# BlinkyBoard.net
KiCad netlist of a schematic drawn in EAGLE
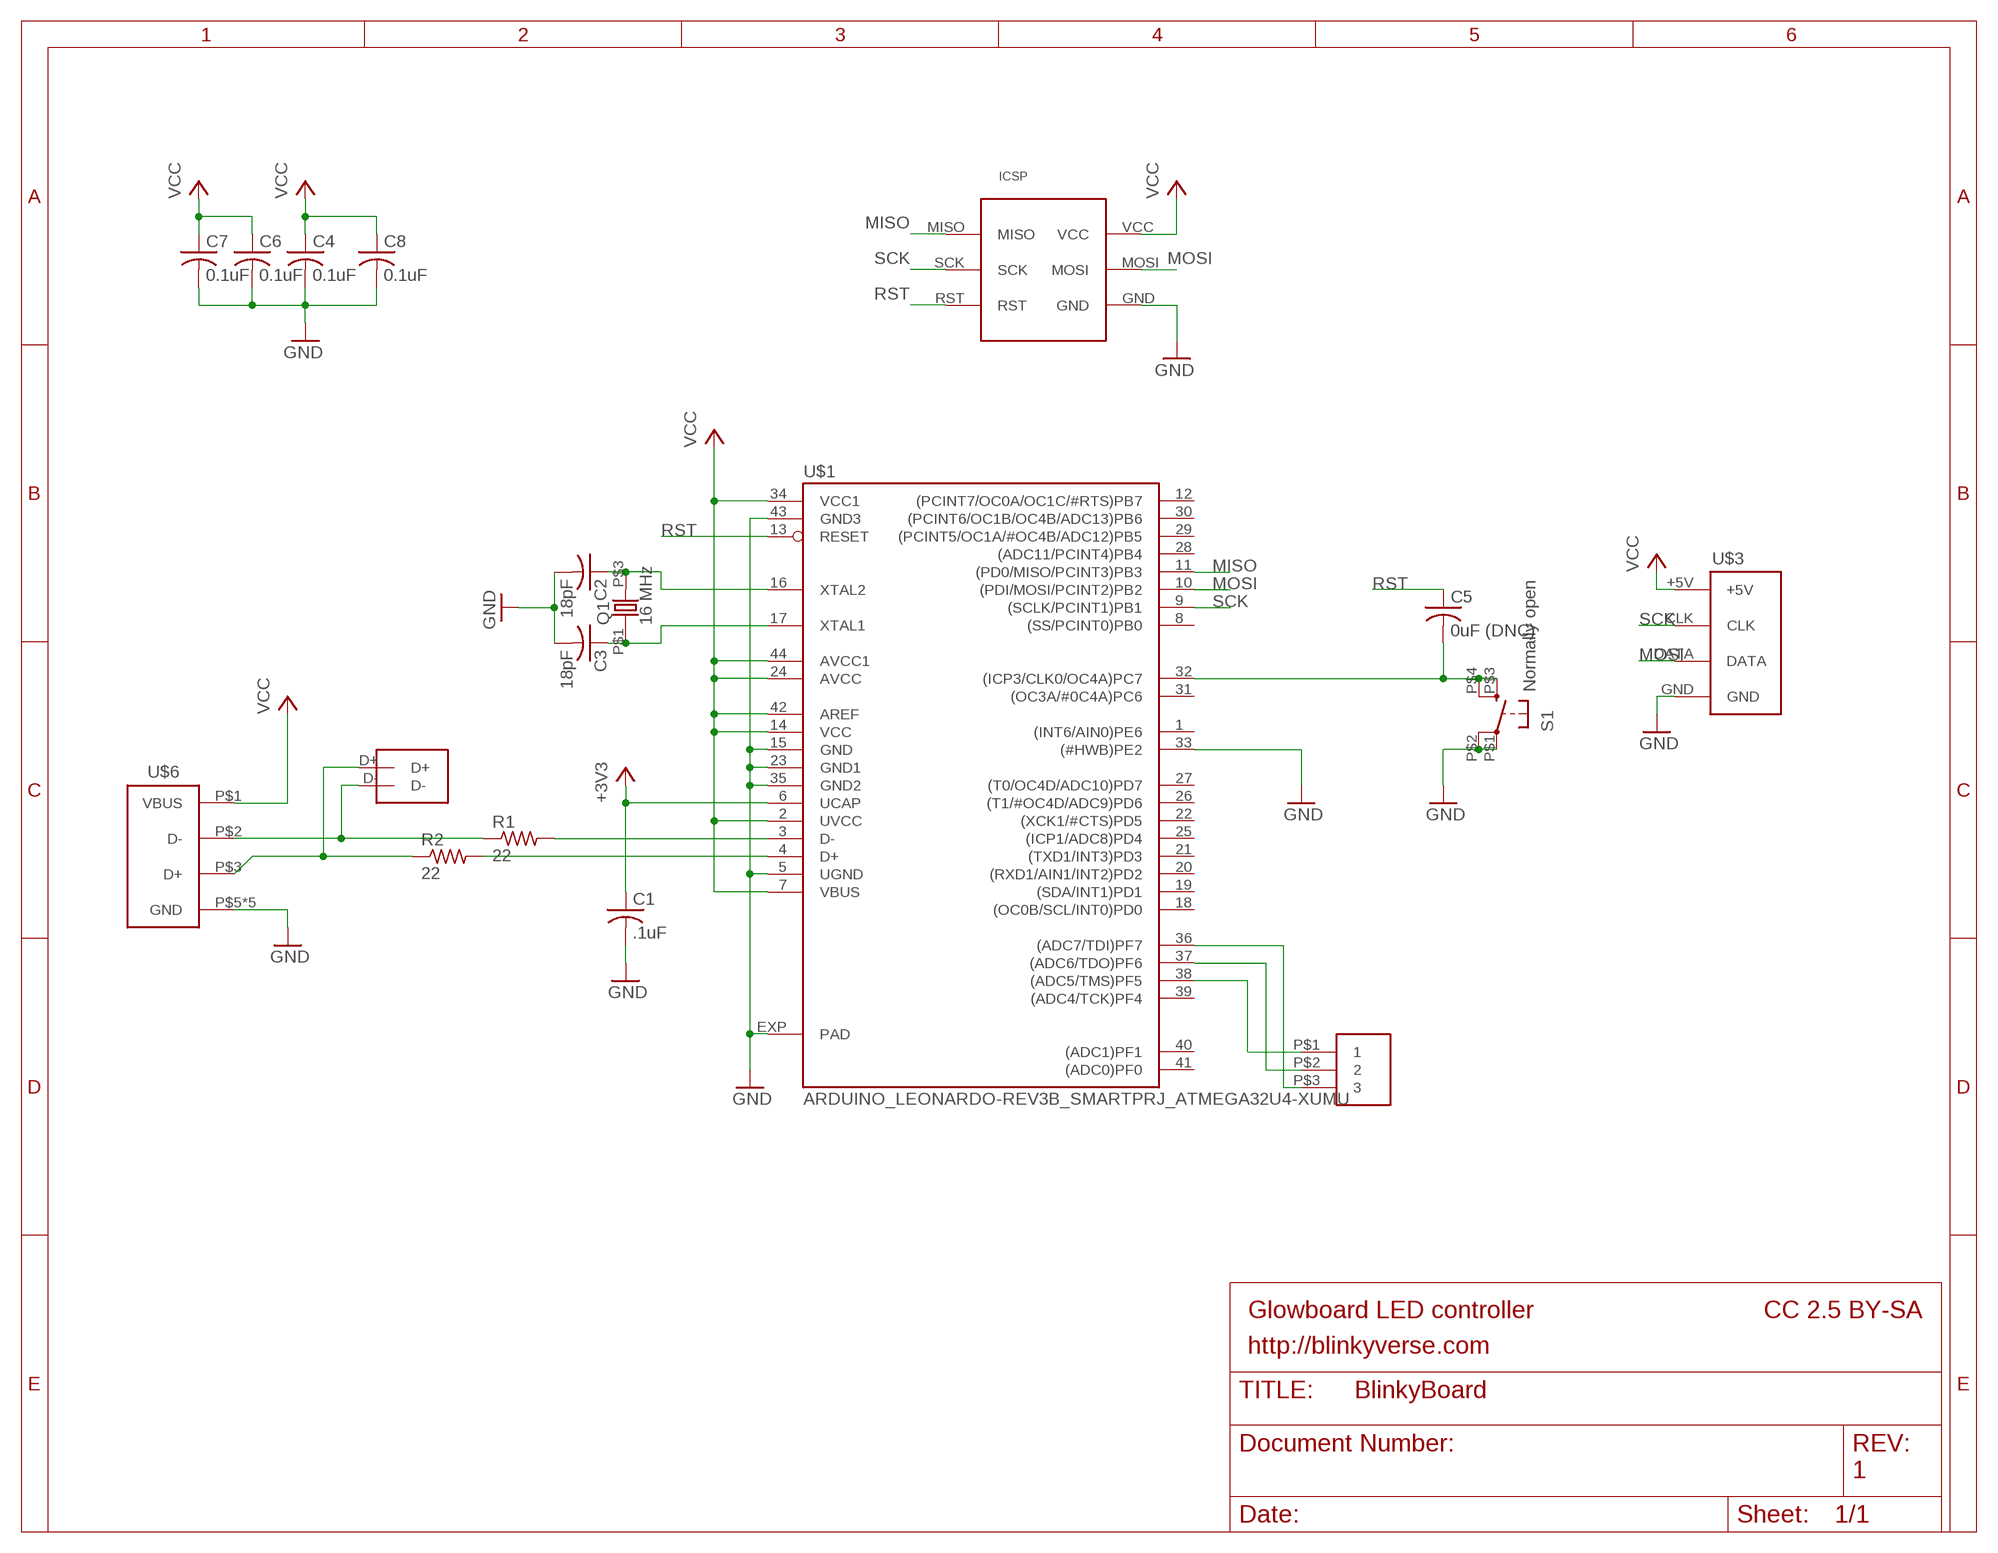
[diagram p0: schematic, sheet 1]

(export (version "E")
  (design (tool "Eeschema 10.0.6"))
  (components
    (comp (ref "C1")
      (value ".1uF")
      (footprint "eagle-import:C0805K")
      (libsource (lib "eagle-import") (part "C-USC0805K"))
    )
    (comp (ref "C2")
      (value "18pF")
      (footprint "eagle-import:C0805K")
      (libsource (lib "eagle-import") (part "C-USC0805K"))
    )
    (comp (ref "C3")
      (value "18pF")
      (footprint "eagle-import:C0805K")
      (libsource (lib "eagle-import") (part "C-USC0805K"))
    )
    (comp (ref "C4")
      (value "0.1uF")
      (footprint "eagle-import:C0805K")
      (libsource (lib "eagle-import") (part "C-USC0805K"))
    )
    (comp (ref "C5")
      (value "0uF (DNC)")
      (footprint "eagle-import:C0805K")
      (libsource (lib "eagle-import") (part "C-USC0805K"))
    )
    (comp (ref "C6")
      (value "0.1uF")
      (footprint "eagle-import:C0805K")
      (libsource (lib "eagle-import") (part "C-USC0805K"))
    )
    (comp (ref "C7")
      (value "0.1uF")
      (footprint "eagle-import:C0805K")
      (libsource (lib "eagle-import") (part "C-USC0805K"))
    )
    (comp (ref "C8")
      (value "0.1uF")
      (footprint "eagle-import:C0805K")
      (libsource (lib "eagle-import") (part "C-USC0805K"))
    )
    (comp (ref "Q1")
      (value "16 MHz")
      (footprint "eagle-import:ABMM2_CRYSTAL")
      (libsource (lib "eagle-import") (part "ABMM2"))
    )
    (comp (ref "R1")
      (value "22")
      (footprint "eagle-import:ADAFRUIT_R0805")
      (libsource (lib "eagle-import") (part "RESISTOR_0805"))
    )
    (comp (ref "R2")
      (value "22")
      (footprint "eagle-import:ADAFRUIT_R0805")
      (libsource (lib "eagle-import") (part "RESISTOR_0805"))
    )
    (comp (ref "S1")
      (value "Normally open")
      (footprint "eagle-import:GLOWBOARD_KMR211G_SWITCH")
      (libsource (lib "eagle-import") (part "GLOWBOARD_KMR211G"))
    )
    (comp (ref "U$1")
      (value "ARDUINO_LEONARDO-REV3B_SMARTPRJ_ATMEGA32U4-XUMU")
      (footprint "eagle-import:ARDUINO_LEONARDO-REV3B_SMARTPRJ_QFN44ML7X7")
      (libsource (lib "eagle-import") (part "ARDUINO_LEONARDO-REV3B_SMARTPRJ_ATMEGA32U4-XUMU"))
    )
    (comp (ref "U$2")
      (value "GLOWBOARD_USB_TEST_PADS")
      (footprint "eagle-import:GLOWBOARD_USB_TEST_PADS")
      (libsource (lib "eagle-import") (part "GLOWBOARD_USB_TEST_PADS"))
    )
    (comp (ref "U$3")
      (value "GLOWBOARD_PAD_CONNECTION")
      (footprint "eagle-import:GLOWBOARD_PAD_CONNECTION")
      (libsource (lib "eagle-import") (part "GLOWBOARD_PAD_CONNECTION"))
    )
    (comp (ref "U$4")
      (value "GLOWBOARD_ICSP")
      (footprint "eagle-import:GLOWBOARD_ICSP_PADS")
      (libsource (lib "eagle-import") (part "GLOWBOARD_ICSP"))
    )
    (comp (ref "U$5")
      (value "GLOWBOARD_EXPANSION_HEADER")
      (footprint "eagle-import:GLOWBOARD_EXPANSION_HEADER")
      (libsource (lib "eagle-import") (part "GLOWBOARD_EXPANSION_HEADER"))
    )
    (comp (ref "U$6")
      (value "GLOWBOARD_MINI_USB")
      (footprint "eagle-import:GLOWBOARD_MINI_USB_PADS")
      (libsource (lib "eagle-import") (part "GLOWBOARD_MINI_USB"))
    )
  )
  (nets
    (net (code "1") (name "+3V3") (class "Default")
      (node (ref "C1") (pin "1") (pinfunction "1_1") (pintype "passive"))
      (node (ref "U$1") (pin "6") (pinfunction "UCAP_6") (pintype "passive"))
    )
    (net (code "2") (name "/MISO") (class "Default")
      (node (ref "U$1") (pin "11") (pinfunction "(PD0/MISO/PCINT3)PB3_11") (pintype "bidirectional"))
      (node (ref "U$4") (pin "MISO") (pinfunction "MISO_MISO") (pintype "bidirectional"))
    )
    (net (code "3") (name "/MOSI") (class "Default")
      (node (ref "U$1") (pin "10") (pinfunction "(PDI/MOSI/PCINT2)PB2_10") (pintype "bidirectional"))
      (node (ref "U$3") (pin "DATA") (pinfunction "DATA_DATA") (pintype "bidirectional"))
      (node (ref "U$4") (pin "MOSI") (pinfunction "MOSI_MOSI") (pintype "bidirectional"))
    )
    (net (code "4") (name "/RST") (class "Default")
      (node (ref "C5") (pin "1") (pinfunction "1_1") (pintype "passive"))
      (node (ref "U$1") (pin "13") (pinfunction "RESET_13") (pintype "input"))
      (node (ref "U$4") (pin "RST") (pinfunction "RST_RST") (pintype "bidirectional"))
    )
    (net (code "5") (name "/SCK") (class "Default")
      (node (ref "U$1") (pin "9") (pinfunction "(SCLK/PCINT1)PB1_9") (pintype "bidirectional"))
      (node (ref "U$3") (pin "CLK") (pinfunction "CLK_CLK") (pintype "bidirectional"))
      (node (ref "U$4") (pin "SCK") (pinfunction "SCK_SCK") (pintype "bidirectional"))
    )
    (net (code "6") (name "GND") (class "Default")
      (node (ref "C1") (pin "2") (pinfunction "2_2") (pintype "passive"))
      (node (ref "C2") (pin "2") (pinfunction "2_2") (pintype "passive"))
      (node (ref "C3") (pin "2") (pinfunction "2_2") (pintype "passive"))
      (node (ref "C4") (pin "2") (pinfunction "2_2") (pintype "passive"))
      (node (ref "C6") (pin "2") (pinfunction "2_2") (pintype "passive"))
      (node (ref "C7") (pin "2") (pinfunction "2_2") (pintype "passive"))
      (node (ref "C8") (pin "2") (pinfunction "2_2") (pintype "passive"))
      (node (ref "S1") (pin "P$1") (pinfunction "P_P$1") (pintype "passive"))
      (node (ref "S1") (pin "P$2") (pinfunction "P1_P$2") (pintype "passive"))
      (node (ref "U$1") (pin "15") (pinfunction "GND_15") (pintype "power_in"))
      (node (ref "U$1") (pin "23") (pinfunction "GND1_23") (pintype "power_in"))
      (node (ref "U$1") (pin "33") (pinfunction "(#HWB)PE2_33") (pintype "bidirectional"))
      (node (ref "U$1") (pin "35") (pinfunction "GND2_35") (pintype "power_in"))
      (node (ref "U$1") (pin "43") (pinfunction "GND3_43") (pintype "power_in"))
      (node (ref "U$1") (pin "5") (pinfunction "UGND_5") (pintype "power_in"))
      (node (ref "U$1") (pin "EXP") (pinfunction "PAD_EXP") (pintype "power_in"))
      (node (ref "U$3") (pin "GND") (pinfunction "GND_GND") (pintype "bidirectional"))
      (node (ref "U$4") (pin "GND") (pinfunction "GND_GND") (pintype "bidirectional"))
      (node (ref "U$6") (pin "P$5") (pinfunction "GND_P$5") (pintype "bidirectional"))
      (node (ref "U$6") (pin "P$6") (pinfunction "GND_P$6") (pintype "bidirectional"))
      (node (ref "U$6") (pin "P$7") (pinfunction "GND_P$7") (pintype "bidirectional"))
      (node (ref "U$6") (pin "P$8") (pinfunction "GND_P$8") (pintype "bidirectional"))
      (node (ref "U$6") (pin "P$9") (pinfunction "GND_P$9") (pintype "bidirectional"))
    )
    (net (code "7") (name "Net-(Q1-1)") (class "Default")
      (node (ref "C3") (pin "1") (pinfunction "1_1") (pintype "passive"))
      (node (ref "Q1") (pin "P$1") (pinfunction "1_P$1") (pintype "passive"))
      (node (ref "U$1") (pin "17") (pinfunction "XTAL1_17") (pintype "bidirectional"))
    )
    (net (code "8") (name "Net-(Q1-2)") (class "Default")
      (node (ref "C2") (pin "1") (pinfunction "1_1") (pintype "passive"))
      (node (ref "Q1") (pin "P$3") (pinfunction "2_P$3") (pintype "passive"))
      (node (ref "U$1") (pin "16") (pinfunction "XTAL2_16") (pintype "bidirectional"))
    )
    (net (code "9") (name "Net-(S1-S)") (class "Default")
      (node (ref "C5") (pin "2") (pinfunction "2_2") (pintype "passive"))
      (node (ref "S1") (pin "P$3") (pinfunction "S_P$3") (pintype "passive"))
      (node (ref "S1") (pin "P$4") (pinfunction "S1_P$4") (pintype "passive"))
      (node (ref "U$1") (pin "32") (pinfunction "(ICP3/CLK0/OC4A)PC7_32") (pintype "bidirectional"))
    )
    (net (code "10") (name "Net-(U$1-(ADC5{slash}TMS)PF5)") (class "Default")
      (node (ref "U$1") (pin "38") (pinfunction "(ADC5/TMS)PF5_38") (pintype "bidirectional"))
      (node (ref "U$5") (pin "P$1") (pinfunction "1_P$1") (pintype "bidirectional"))
    )
    (net (code "11") (name "Net-(U$1-(ADC6{slash}TDO)PF6)") (class "Default")
      (node (ref "U$1") (pin "37") (pinfunction "(ADC6/TDO)PF6_37") (pintype "bidirectional"))
      (node (ref "U$5") (pin "P$2") (pinfunction "2_P$2") (pintype "bidirectional"))
    )
    (net (code "12") (name "Net-(U$1-(ADC7{slash}TDI)PF7)") (class "Default")
      (node (ref "U$1") (pin "36") (pinfunction "(ADC7/TDI)PF7_36") (pintype "bidirectional"))
      (node (ref "U$5") (pin "P$3") (pinfunction "3_P$3") (pintype "bidirectional"))
    )
    (net (code "13") (name "Net-(U$1-D+)") (class "Default")
      (node (ref "R2") (pin "2") (pinfunction "2_2") (pintype "passive"))
      (node (ref "U$1") (pin "4") (pinfunction "D+_4") (pintype "bidirectional"))
    )
    (net (code "14") (name "Net-(U$1-D-)") (class "Default")
      (node (ref "R1") (pin "2") (pinfunction "2_2") (pintype "passive"))
      (node (ref "U$1") (pin "3") (pinfunction "D-_3") (pintype "bidirectional"))
    )
    (net (code "15") (name "Net-(U$6-D+)") (class "Default")
      (node (ref "R2") (pin "1") (pinfunction "1_1") (pintype "passive"))
      (node (ref "U$2") (pin "D+") (pinfunction "D+_D+") (pintype "bidirectional"))
      (node (ref "U$6") (pin "P$3") (pinfunction "D+_P$3") (pintype "bidirectional"))
    )
    (net (code "16") (name "Net-(U$6-D-)") (class "Default")
      (node (ref "R1") (pin "1") (pinfunction "1_1") (pintype "passive"))
      (node (ref "U$2") (pin "D-") (pinfunction "D-_D-") (pintype "bidirectional"))
      (node (ref "U$6") (pin "P$2") (pinfunction "D-_P$2") (pintype "bidirectional"))
    )
    (net (code "17") (name "VCC") (class "Default")
      (node (ref "C4") (pin "1") (pinfunction "1_1") (pintype "passive"))
      (node (ref "C6") (pin "1") (pinfunction "1_1") (pintype "passive"))
      (node (ref "C7") (pin "1") (pinfunction "1_1") (pintype "passive"))
      (node (ref "C8") (pin "1") (pinfunction "1_1") (pintype "passive"))
      (node (ref "U$1") (pin "14") (pinfunction "VCC_14") (pintype "power_in"))
      (node (ref "U$1") (pin "2") (pinfunction "UVCC_2") (pintype "power_in"))
      (node (ref "U$1") (pin "24") (pinfunction "AVCC_24") (pintype "power_in"))
      (node (ref "U$1") (pin "34") (pinfunction "VCC1_34") (pintype "power_in"))
      (node (ref "U$1") (pin "42") (pinfunction "AREF_42") (pintype "power_in"))
      (node (ref "U$1") (pin "44") (pinfunction "AVCC1_44") (pintype "power_in"))
      (node (ref "U$1") (pin "7") (pinfunction "VBUS_7") (pintype "input"))
      (node (ref "U$3") (pin "+5V") (pinfunction "+5V_+5V") (pintype "bidirectional"))
      (node (ref "U$4") (pin "VCC") (pinfunction "VCC_VCC") (pintype "bidirectional"))
      (node (ref "U$6") (pin "P$1") (pinfunction "VBUS_P$1") (pintype "bidirectional"))
    )
    (net (code "18") (name "unconnected-(U$1-(ADC0)PF0-Pad41)") (class "Default")
      (node (ref "U$1") (pin "41") (pinfunction "(ADC0)PF0_41") (pintype "bidirectional"))
    )
    (net (code "19") (name "unconnected-(U$1-(ADC1)PF1-Pad40)") (class "Default")
      (node (ref "U$1") (pin "40") (pinfunction "(ADC1)PF1_40") (pintype "bidirectional"))
    )
    (net (code "20") (name "unconnected-(U$1-(ADC4{slash}TCK)PF4-Pad39)") (class "Default")
      (node (ref "U$1") (pin "39") (pinfunction "(ADC4/TCK)PF4_39") (pintype "bidirectional"))
    )
    (net (code "21") (name "unconnected-(U$1-(ADC11{slash}PCINT4)PB4-Pad28)") (class "Default")
      (node (ref "U$1") (pin "28") (pinfunction "(ADC11/PCINT4)PB4_28") (pintype "bidirectional"))
    )
    (net (code "22") (name "unconnected-(U$1-(ICP1{slash}ADC8)PD4-Pad25)") (class "Default")
      (node (ref "U$1") (pin "25") (pinfunction "(ICP1/ADC8)PD4_25") (pintype "bidirectional"))
    )
    (net (code "23") (name "unconnected-(U$1-(INT6{slash}AIN0)PE6-Pad1)") (class "Default")
      (node (ref "U$1") (pin "1") (pinfunction "(INT6/AIN0)PE6_1") (pintype "bidirectional"))
    )
    (net (code "24") (name "unconnected-(U$1-(OC0B{slash}SCL{slash}INT0)PD0-Pad18)") (class "Default")
      (node (ref "U$1") (pin "18") (pinfunction "(OC0B/SCL/INT0)PD0_18") (pintype "bidirectional"))
    )
    (net (code "25") (name "unconnected-(U$1-(OC3A{slash}#0C4A)PC6-Pad31)") (class "Default")
      (node (ref "U$1") (pin "31") (pinfunction "(OC3A/#0C4A)PC6_31") (pintype "bidirectional"))
    )
    (net (code "26") (name "unconnected-(U$1-(PCINT5{slash}OC1A{slash}#OC4B{slash}ADC12)PB5-Pad29)") (class "Default")
      (node (ref "U$1") (pin "29") (pinfunction "(PCINT5/OC1A/#OC4B/ADC12)PB5_29") (pintype "bidirectional"))
    )
    (net (code "27") (name "unconnected-(U$1-(PCINT6{slash}OC1B{slash}OC4B{slash}ADC13)PB6-Pad30)") (class "Default")
      (node (ref "U$1") (pin "30") (pinfunction "(PCINT6/OC1B/OC4B/ADC13)PB6_30") (pintype "bidirectional"))
    )
    (net (code "28") (name "unconnected-(U$1-(PCINT7{slash}OC0A{slash}OC1C{slash}#RTS)PB7-Pad12)") (class "Default")
      (node (ref "U$1") (pin "12") (pinfunction "(PCINT7/OC0A/OC1C/#RTS)PB7_12") (pintype "bidirectional"))
    )
    (net (code "29") (name "unconnected-(U$1-(RXD1{slash}AIN1{slash}INT2)PD2-Pad20)") (class "Default")
      (node (ref "U$1") (pin "20") (pinfunction "(RXD1/AIN1/INT2)PD2_20") (pintype "bidirectional"))
    )
    (net (code "30") (name "unconnected-(U$1-(SDA{slash}INT1)PD1-Pad19)") (class "Default")
      (node (ref "U$1") (pin "19") (pinfunction "(SDA/INT1)PD1_19") (pintype "bidirectional"))
    )
    (net (code "31") (name "unconnected-(U$1-(SS{slash}PCINT0)PB0-Pad8)") (class "Default")
      (node (ref "U$1") (pin "8") (pinfunction "(SS/PCINT0)PB0_8") (pintype "bidirectional"))
    )
    (net (code "32") (name "unconnected-(U$1-(T0{slash}OC4D{slash}ADC10)PD7-Pad27)") (class "Default")
      (node (ref "U$1") (pin "27") (pinfunction "(T0/OC4D/ADC10)PD7_27") (pintype "bidirectional"))
    )
    (net (code "33") (name "unconnected-(U$1-(T1{slash}#OC4D{slash}ADC9)PD6-Pad26)") (class "Default")
      (node (ref "U$1") (pin "26") (pinfunction "(T1/#OC4D/ADC9)PD6_26") (pintype "bidirectional"))
    )
    (net (code "34") (name "unconnected-(U$1-(TXD1{slash}INT3)PD3-Pad21)") (class "Default")
      (node (ref "U$1") (pin "21") (pinfunction "(TXD1/INT3)PD3_21") (pintype "bidirectional"))
    )
    (net (code "35") (name "unconnected-(U$1-(XCK1{slash}#CTS)PD5-Pad22)") (class "Default")
      (node (ref "U$1") (pin "22") (pinfunction "(XCK1/#CTS)PD5_22") (pintype "bidirectional"))
    )
  )
)
